# jammer.net
KiCad netlist of a schematic drawn in Altium Designer
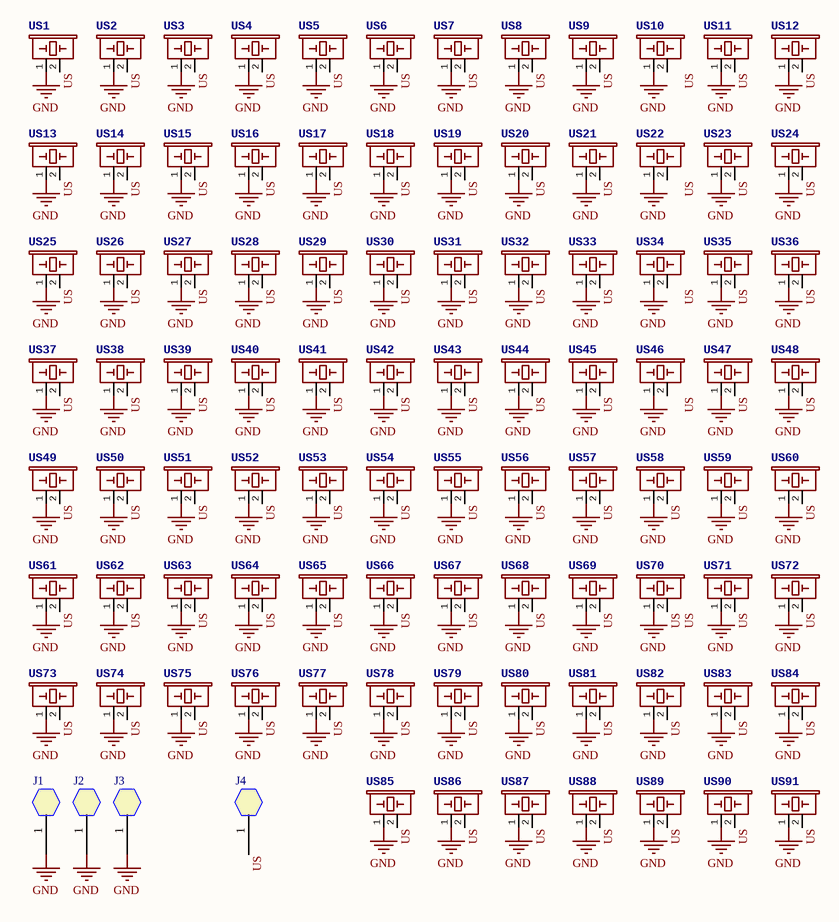
[diagram p0: jammer.SchDoc]

(export (version "E")
  (design (tool "Eeschema 10.0.6"))
  (components
    (comp (ref "J1")
      (value "NutSolder")
      (footprint "NutSolder")
      (libsource (lib "400PT160_2") (part "NutSolder"))
    )
    (comp (ref "J2")
      (value "NutSolder")
      (footprint "NutSolder")
      (libsource (lib "400PT160_2") (part "NutSolder"))
    )
    (comp (ref "J3")
      (value "NutSolder")
      (footprint "NutSolder")
      (libsource (lib "400PT160_2") (part "NutSolder"))
    )
    (comp (ref "J4")
      (value "NutSolder")
      (footprint "NutSolder")
      (libsource (lib "400PT160_2") (part "NutSolder"))
    )
    (comp (ref "US1")
      (value "Comment")
      (footprint "400PT1601")
      (fields (field (name "MP") "400PT160") (field (name "MF") "Prowave"))
      (libsource (lib "400PT160") (part "400PT160"))
    )
    (comp (ref "US2")
      (value "~")
      (footprint "400PT1601")
      (fields (field (name "MP") "400PT160") (field (name "MF") "Prowave"))
      (libsource (lib "400PT160") (part "400PT160"))
    )
    (comp (ref "US3")
      (value "Comment")
      (footprint "400PT1601")
      (fields (field (name "MP") "400PT160") (field (name "MF") "Prowave"))
      (libsource (lib "400PT160") (part "400PT160"))
    )
    (comp (ref "US4")
      (value "Comment")
      (footprint "400PT1601")
      (fields (field (name "MP") "400PT160") (field (name "MF") "Prowave"))
      (libsource (lib "400PT160") (part "400PT160"))
    )
    (comp (ref "US5")
      (value "Comment")
      (footprint "400PT1601")
      (fields (field (name "MP") "400PT160") (field (name "MF") "Prowave"))
      (libsource (lib "400PT160") (part "400PT160"))
    )
    (comp (ref "US6")
      (value "Comment")
      (footprint "400PT1601")
      (fields (field (name "MP") "400PT160") (field (name "MF") "Prowave"))
      (libsource (lib "400PT160") (part "400PT160"))
    )
    (comp (ref "US7")
      (value "Comment")
      (footprint "400PT1601")
      (fields (field (name "MP") "400PT160") (field (name "MF") "Prowave"))
      (libsource (lib "400PT160") (part "400PT160"))
    )
    (comp (ref "US8")
      (value "Comment")
      (footprint "400PT1601")
      (fields (field (name "MP") "400PT160") (field (name "MF") "Prowave"))
      (libsource (lib "400PT160") (part "400PT160"))
    )
    (comp (ref "US9")
      (value "Comment")
      (footprint "400PT1601")
      (fields (field (name "MP") "400PT160") (field (name "MF") "Prowave"))
      (libsource (lib "400PT160") (part "400PT160"))
    )
    (comp (ref "US10")
      (value "Comment")
      (footprint "400PT1601")
      (fields (field (name "MP") "400PT160") (field (name "MF") "Prowave"))
      (libsource (lib "400PT160") (part "400PT160"))
    )
    (comp (ref "US11")
      (value "Comment")
      (footprint "400PT1601")
      (fields (field (name "MP") "400PT160") (field (name "MF") "Prowave"))
      (libsource (lib "400PT160") (part "400PT160"))
    )
    (comp (ref "US12")
      (value "Comment")
      (footprint "400PT1601")
      (fields (field (name "MP") "400PT160") (field (name "MF") "Prowave"))
      (libsource (lib "400PT160") (part "400PT160"))
    )
    (comp (ref "US13")
      (value "Comment")
      (footprint "400PT1601")
      (fields (field (name "MP") "400PT160") (field (name "MF") "Prowave"))
      (libsource (lib "400PT160") (part "400PT160"))
    )
    (comp (ref "US14")
      (value "Comment")
      (footprint "400PT1601")
      (fields (field (name "MP") "400PT160") (field (name "MF") "Prowave"))
      (libsource (lib "400PT160") (part "400PT160"))
    )
    (comp (ref "US15")
      (value "Comment")
      (footprint "400PT1601")
      (fields (field (name "MP") "400PT160") (field (name "MF") "Prowave"))
      (libsource (lib "400PT160") (part "400PT160"))
    )
    (comp (ref "US16")
      (value "Comment")
      (footprint "400PT1601")
      (fields (field (name "MP") "400PT160") (field (name "MF") "Prowave"))
      (libsource (lib "400PT160") (part "400PT160"))
    )
    (comp (ref "US17")
      (value "Comment")
      (footprint "400PT1601")
      (fields (field (name "MP") "400PT160") (field (name "MF") "Prowave"))
      (libsource (lib "400PT160") (part "400PT160"))
    )
    (comp (ref "US18")
      (value "Comment")
      (footprint "400PT1601")
      (fields (field (name "MP") "400PT160") (field (name "MF") "Prowave"))
      (libsource (lib "400PT160") (part "400PT160"))
    )
    (comp (ref "US19")
      (value "Comment")
      (footprint "400PT1601")
      (fields (field (name "MP") "400PT160") (field (name "MF") "Prowave"))
      (libsource (lib "400PT160") (part "400PT160"))
    )
    (comp (ref "US20")
      (value "Comment")
      (footprint "400PT1601")
      (fields (field (name "MP") "400PT160") (field (name "MF") "Prowave"))
      (libsource (lib "400PT160") (part "400PT160"))
    )
    (comp (ref "US21")
      (value "Comment")
      (footprint "400PT1601")
      (fields (field (name "MP") "400PT160") (field (name "MF") "Prowave"))
      (libsource (lib "400PT160") (part "400PT160"))
    )
    (comp (ref "US22")
      (value "Comment")
      (footprint "400PT1601")
      (fields (field (name "MP") "400PT160") (field (name "MF") "Prowave"))
      (libsource (lib "400PT160") (part "400PT160"))
    )
    (comp (ref "US23")
      (value "Comment")
      (footprint "400PT1601")
      (fields (field (name "MP") "400PT160") (field (name "MF") "Prowave"))
      (libsource (lib "400PT160") (part "400PT160"))
    )
    (comp (ref "US24")
      (value "Comment")
      (footprint "400PT1601")
      (fields (field (name "MP") "400PT160") (field (name "MF") "Prowave"))
      (libsource (lib "400PT160") (part "400PT160"))
    )
    (comp (ref "US25")
      (value "Comment")
      (footprint "400PT1601")
      (fields (field (name "MP") "400PT160") (field (name "MF") "Prowave"))
      (libsource (lib "400PT160") (part "400PT160"))
    )
    (comp (ref "US26")
      (value "~")
      (footprint "400PT1601")
      (fields (field (name "MP") "400PT160") (field (name "MF") "Prowave"))
      (libsource (lib "400PT160") (part "400PT160"))
    )
    (comp (ref "US27")
      (value "Comment")
      (footprint "400PT1601")
      (fields (field (name "MP") "400PT160") (field (name "MF") "Prowave"))
      (libsource (lib "400PT160") (part "400PT160"))
    )
    (comp (ref "US28")
      (value "Comment")
      (footprint "400PT1601")
      (fields (field (name "MP") "400PT160") (field (name "MF") "Prowave"))
      (libsource (lib "400PT160") (part "400PT160"))
    )
    (comp (ref "US29")
      (value "Comment")
      (footprint "400PT1601")
      (fields (field (name "MP") "400PT160") (field (name "MF") "Prowave"))
      (libsource (lib "400PT160") (part "400PT160"))
    )
    (comp (ref "US30")
      (value "Comment")
      (footprint "400PT1601")
      (fields (field (name "MP") "400PT160") (field (name "MF") "Prowave"))
      (libsource (lib "400PT160") (part "400PT160"))
    )
    (comp (ref "US31")
      (value "Comment")
      (footprint "400PT1601")
      (fields (field (name "MP") "400PT160") (field (name "MF") "Prowave"))
      (libsource (lib "400PT160") (part "400PT160"))
    )
    (comp (ref "US32")
      (value "Comment")
      (footprint "400PT1601")
      (fields (field (name "MP") "400PT160") (field (name "MF") "Prowave"))
      (libsource (lib "400PT160") (part "400PT160"))
    )
    (comp (ref "US33")
      (value "Comment")
      (footprint "400PT1601")
      (fields (field (name "MP") "400PT160") (field (name "MF") "Prowave"))
      (libsource (lib "400PT160") (part "400PT160"))
    )
    (comp (ref "US34")
      (value "Comment")
      (footprint "400PT1601")
      (fields (field (name "MP") "400PT160") (field (name "MF") "Prowave"))
      (libsource (lib "400PT160") (part "400PT160"))
    )
    (comp (ref "US35")
      (value "Comment")
      (footprint "400PT1601")
      (fields (field (name "MP") "400PT160") (field (name "MF") "Prowave"))
      (libsource (lib "400PT160") (part "400PT160"))
    )
    (comp (ref "US36")
      (value "Comment")
      (footprint "400PT1601")
      (fields (field (name "MP") "400PT160") (field (name "MF") "Prowave"))
      (libsource (lib "400PT160") (part "400PT160"))
    )
    (comp (ref "US37")
      (value "Comment")
      (footprint "400PT1601")
      (fields (field (name "MP") "400PT160") (field (name "MF") "Prowave"))
      (libsource (lib "400PT160") (part "400PT160"))
    )
    (comp (ref "US38")
      (value "Comment")
      (footprint "400PT1601")
      (fields (field (name "MP") "400PT160") (field (name "MF") "Prowave"))
      (libsource (lib "400PT160") (part "400PT160"))
    )
    (comp (ref "US39")
      (value "Comment")
      (footprint "400PT1601")
      (fields (field (name "MP") "400PT160") (field (name "MF") "Prowave"))
      (libsource (lib "400PT160") (part "400PT160"))
    )
    (comp (ref "US40")
      (value "Comment")
      (footprint "400PT1601")
      (fields (field (name "MP") "400PT160") (field (name "MF") "Prowave"))
      (libsource (lib "400PT160") (part "400PT160"))
    )
    (comp (ref "US41")
      (value "Comment")
      (footprint "400PT1601")
      (fields (field (name "MP") "400PT160") (field (name "MF") "Prowave"))
      (libsource (lib "400PT160") (part "400PT160"))
    )
    (comp (ref "US42")
      (value "Comment")
      (footprint "400PT1601")
      (fields (field (name "MP") "400PT160") (field (name "MF") "Prowave"))
      (libsource (lib "400PT160") (part "400PT160"))
    )
    (comp (ref "US43")
      (value "Comment")
      (footprint "400PT1601")
      (fields (field (name "MP") "400PT160") (field (name "MF") "Prowave"))
      (libsource (lib "400PT160") (part "400PT160"))
    )
    (comp (ref "US44")
      (value "Comment")
      (footprint "400PT1601")
      (fields (field (name "MP") "400PT160") (field (name "MF") "Prowave"))
      (libsource (lib "400PT160") (part "400PT160"))
    )
    (comp (ref "US45")
      (value "Comment")
      (footprint "400PT1601")
      (fields (field (name "MP") "400PT160") (field (name "MF") "Prowave"))
      (libsource (lib "400PT160") (part "400PT160"))
    )
    (comp (ref "US46")
      (value "Comment")
      (footprint "400PT1601")
      (fields (field (name "MP") "400PT160") (field (name "MF") "Prowave"))
      (libsource (lib "400PT160") (part "400PT160"))
    )
    (comp (ref "US47")
      (value "Comment")
      (footprint "400PT1601")
      (fields (field (name "MP") "400PT160") (field (name "MF") "Prowave"))
      (libsource (lib "400PT160") (part "400PT160"))
    )
    (comp (ref "US48")
      (value "Comment")
      (footprint "400PT1601")
      (fields (field (name "MP") "400PT160") (field (name "MF") "Prowave"))
      (libsource (lib "400PT160") (part "400PT160"))
    )
    (comp (ref "US49")
      (value "Comment")
      (footprint "400PT1601")
      (fields (field (name "MP") "400PT160") (field (name "MF") "Prowave"))
      (libsource (lib "400PT160") (part "400PT160"))
    )
    (comp (ref "US50")
      (value "~")
      (footprint "400PT1601")
      (fields (field (name "MP") "400PT160") (field (name "MF") "Prowave"))
      (libsource (lib "400PT160") (part "400PT160"))
    )
    (comp (ref "US51")
      (value "Comment")
      (footprint "400PT1601")
      (fields (field (name "MP") "400PT160") (field (name "MF") "Prowave"))
      (libsource (lib "400PT160") (part "400PT160"))
    )
    (comp (ref "US52")
      (value "Comment")
      (footprint "400PT1601")
      (fields (field (name "MP") "400PT160") (field (name "MF") "Prowave"))
      (libsource (lib "400PT160") (part "400PT160"))
    )
    (comp (ref "US53")
      (value "Comment")
      (footprint "400PT1601")
      (fields (field (name "MP") "400PT160") (field (name "MF") "Prowave"))
      (libsource (lib "400PT160") (part "400PT160"))
    )
    (comp (ref "US54")
      (value "Comment")
      (footprint "400PT1601")
      (fields (field (name "MP") "400PT160") (field (name "MF") "Prowave"))
      (libsource (lib "400PT160") (part "400PT160"))
    )
    (comp (ref "US55")
      (value "Comment")
      (footprint "400PT1601")
      (fields (field (name "MP") "400PT160") (field (name "MF") "Prowave"))
      (libsource (lib "400PT160") (part "400PT160"))
    )
    (comp (ref "US56")
      (value "Comment")
      (footprint "400PT1601")
      (fields (field (name "MP") "400PT160") (field (name "MF") "Prowave"))
      (libsource (lib "400PT160") (part "400PT160"))
    )
    (comp (ref "US57")
      (value "Comment")
      (footprint "400PT1601")
      (fields (field (name "MP") "400PT160") (field (name "MF") "Prowave"))
      (libsource (lib "400PT160") (part "400PT160"))
    )
    (comp (ref "US58")
      (value "Comment")
      (footprint "400PT1601")
      (fields (field (name "MP") "400PT160") (field (name "MF") "Prowave"))
      (libsource (lib "400PT160") (part "400PT160"))
    )
    (comp (ref "US59")
      (value "Comment")
      (footprint "400PT1601")
      (fields (field (name "MP") "400PT160") (field (name "MF") "Prowave"))
      (libsource (lib "400PT160") (part "400PT160"))
    )
    (comp (ref "US60")
      (value "Comment")
      (footprint "400PT1601")
      (fields (field (name "MP") "400PT160") (field (name "MF") "Prowave"))
      (libsource (lib "400PT160") (part "400PT160"))
    )
    (comp (ref "US61")
      (value "Comment")
      (footprint "400PT1601")
      (fields (field (name "MP") "400PT160") (field (name "MF") "Prowave"))
      (libsource (lib "400PT160") (part "400PT160"))
    )
    (comp (ref "US62")
      (value "Comment")
      (footprint "400PT1601")
      (fields (field (name "MP") "400PT160") (field (name "MF") "Prowave"))
      (libsource (lib "400PT160") (part "400PT160"))
    )
    (comp (ref "US63")
      (value "Comment")
      (footprint "400PT1601")
      (fields (field (name "MP") "400PT160") (field (name "MF") "Prowave"))
      (libsource (lib "400PT160") (part "400PT160"))
    )
    (comp (ref "US64")
      (value "~")
      (footprint "400PT1601")
      (fields (field (name "MP") "400PT160") (field (name "MF") "Prowave"))
      (libsource (lib "400PT160") (part "400PT160"))
    )
    (comp (ref "US65")
      (value "~")
      (footprint "400PT1601")
      (fields (field (name "MP") "400PT160") (field (name "MF") "Prowave"))
      (libsource (lib "400PT160") (part "400PT160"))
    )
    (comp (ref "US66")
      (value "~")
      (footprint "400PT1601")
      (fields (field (name "MP") "400PT160") (field (name "MF") "Prowave"))
      (libsource (lib "400PT160") (part "400PT160"))
    )
    (comp (ref "US67")
      (value "~")
      (footprint "400PT1601")
      (fields (field (name "MP") "400PT160") (field (name "MF") "Prowave"))
      (libsource (lib "400PT160") (part "400PT160"))
    )
    (comp (ref "US68")
      (value "Comment")
      (footprint "400PT1601")
      (fields (field (name "MP") "400PT160") (field (name "MF") "Prowave"))
      (libsource (lib "400PT160") (part "400PT160"))
    )
    (comp (ref "US69")
      (value "Comment")
      (footprint "400PT1601")
      (fields (field (name "MP") "400PT160") (field (name "MF") "Prowave"))
      (libsource (lib "400PT160") (part "400PT160"))
    )
    (comp (ref "US70")
      (value "Comment")
      (footprint "400PT1601")
      (fields (field (name "MP") "400PT160") (field (name "MF") "Prowave"))
      (libsource (lib "400PT160") (part "400PT160"))
    )
    (comp (ref "US71")
      (value "Comment")
      (footprint "400PT1601")
      (fields (field (name "MP") "400PT160") (field (name "MF") "Prowave"))
      (libsource (lib "400PT160") (part "400PT160"))
    )
    (comp (ref "US72")
      (value "Comment")
      (footprint "400PT1601")
      (fields (field (name "MP") "400PT160") (field (name "MF") "Prowave"))
      (libsource (lib "400PT160") (part "400PT160"))
    )
    (comp (ref "US73")
      (value "Comment")
      (footprint "400PT1601")
      (fields (field (name "MP") "400PT160") (field (name "MF") "Prowave"))
      (libsource (lib "400PT160") (part "400PT160"))
    )
    (comp (ref "US74")
      (value "Comment")
      (footprint "400PT1601")
      (fields (field (name "MP") "400PT160") (field (name "MF") "Prowave"))
      (libsource (lib "400PT160") (part "400PT160"))
    )
    (comp (ref "US75")
      (value "Comment")
      (footprint "400PT1601")
      (fields (field (name "MP") "400PT160") (field (name "MF") "Prowave"))
      (libsource (lib "400PT160") (part "400PT160"))
    )
    (comp (ref "US76")
      (value "Comment")
      (footprint "400PT1601")
      (fields (field (name "MP") "400PT160") (field (name "MF") "Prowave"))
      (libsource (lib "400PT160") (part "400PT160"))
    )
    (comp (ref "US77")
      (value "Comment")
      (footprint "400PT1601")
      (fields (field (name "MP") "400PT160") (field (name "MF") "Prowave"))
      (libsource (lib "400PT160") (part "400PT160"))
    )
    (comp (ref "US78")
      (value "Comment")
      (footprint "400PT1601")
      (fields (field (name "MP") "400PT160") (field (name "MF") "Prowave"))
      (libsource (lib "400PT160") (part "400PT160"))
    )
    (comp (ref "US79")
      (value "Comment")
      (footprint "400PT1601")
      (fields (field (name "MP") "400PT160") (field (name "MF") "Prowave"))
      (libsource (lib "400PT160") (part "400PT160"))
    )
    (comp (ref "US80")
      (value "Comment")
      (footprint "400PT1601")
      (fields (field (name "MP") "400PT160") (field (name "MF") "Prowave"))
      (libsource (lib "400PT160") (part "400PT160"))
    )
    (comp (ref "US81")
      (value "Comment")
      (footprint "400PT1601")
      (fields (field (name "MP") "400PT160") (field (name "MF") "Prowave"))
      (libsource (lib "400PT160") (part "400PT160"))
    )
    (comp (ref "US82")
      (value "Comment")
      (footprint "400PT1601")
      (fields (field (name "MP") "400PT160") (field (name "MF") "Prowave"))
      (libsource (lib "400PT160") (part "400PT160"))
    )
    (comp (ref "US83")
      (value "Comment")
      (footprint "400PT1601")
      (fields (field (name "MP") "400PT160") (field (name "MF") "Prowave"))
      (libsource (lib "400PT160") (part "400PT160"))
    )
    (comp (ref "US84")
      (value "Comment")
      (footprint "400PT1601")
      (fields (field (name "MP") "400PT160") (field (name "MF") "Prowave"))
      (libsource (lib "400PT160") (part "400PT160"))
    )
    (comp (ref "US85")
      (value "Comment")
      (footprint "400PT1601")
      (fields (field (name "MP") "400PT160") (field (name "MF") "Prowave"))
      (libsource (lib "400PT160") (part "400PT160"))
    )
    (comp (ref "US86")
      (value "Comment")
      (footprint "400PT1601")
      (fields (field (name "MP") "400PT160") (field (name "MF") "Prowave"))
      (libsource (lib "400PT160") (part "400PT160"))
    )
    (comp (ref "US87")
      (value "Comment")
      (footprint "400PT1601")
      (fields (field (name "MP") "400PT160") (field (name "MF") "Prowave"))
      (libsource (lib "400PT160") (part "400PT160"))
    )
    (comp (ref "US88")
      (value "Comment")
      (footprint "400PT1601")
      (fields (field (name "MP") "400PT160") (field (name "MF") "Prowave"))
      (libsource (lib "400PT160") (part "400PT160"))
    )
    (comp (ref "US89")
      (value "Comment")
      (footprint "400PT1601")
      (fields (field (name "MP") "400PT160") (field (name "MF") "Prowave"))
      (libsource (lib "400PT160") (part "400PT160"))
    )
    (comp (ref "US90")
      (value "Comment")
      (footprint "400PT1601")
      (fields (field (name "MP") "400PT160") (field (name "MF") "Prowave"))
      (libsource (lib "400PT160") (part "400PT160"))
    )
    (comp (ref "US91")
      (value "Comment")
      (footprint "400PT1601")
      (fields (field (name "MP") "400PT160") (field (name "MF") "Prowave"))
      (libsource (lib "400PT160") (part "400PT160"))
    )
  )
  (nets
    (net (code "1") (name "/US") (class "Default")
      (node (ref "J4") (pin "1") (pinfunction "1_1") (pintype "passive"))
      (node (ref "US1") (pin "2") (pinfunction "2_2") (pintype "passive"))
      (node (ref "US11") (pin "2") (pinfunction "2_2") (pintype "passive"))
      (node (ref "US12") (pin "2") (pinfunction "2_2") (pintype "passive"))
      (node (ref "US13") (pin "2") (pinfunction "2_2") (pintype "passive"))
      (node (ref "US14") (pin "2") (pinfunction "2_2") (pintype "passive"))
      (node (ref "US15") (pin "2") (pinfunction "2_2") (pintype "passive"))
      (node (ref "US16") (pin "2") (pinfunction "2_2") (pintype "passive"))
      (node (ref "US17") (pin "2") (pinfunction "2_2") (pintype "passive"))
      (node (ref "US18") (pin "2") (pinfunction "2_2") (pintype "passive"))
      (node (ref "US19") (pin "2") (pinfunction "2_2") (pintype "passive"))
      (node (ref "US2") (pin "2") (pinfunction "2_2") (pintype "passive"))
      (node (ref "US20") (pin "2") (pinfunction "2_2") (pintype "passive"))
      (node (ref "US21") (pin "2") (pinfunction "2_2") (pintype "passive"))
      (node (ref "US23") (pin "2") (pinfunction "2_2") (pintype "passive"))
      (node (ref "US24") (pin "2") (pinfunction "2_2") (pintype "passive"))
      (node (ref "US25") (pin "2") (pinfunction "2_2") (pintype "passive"))
      (node (ref "US26") (pin "2") (pinfunction "2_2") (pintype "passive"))
      (node (ref "US27") (pin "2") (pinfunction "2_2") (pintype "passive"))
      (node (ref "US28") (pin "2") (pinfunction "2_2") (pintype "passive"))
      (node (ref "US29") (pin "2") (pinfunction "2_2") (pintype "passive"))
      (node (ref "US3") (pin "2") (pinfunction "2_2") (pintype "passive"))
      (node (ref "US30") (pin "2") (pinfunction "2_2") (pintype "passive"))
      (node (ref "US31") (pin "2") (pinfunction "2_2") (pintype "passive"))
      (node (ref "US32") (pin "2") (pinfunction "2_2") (pintype "passive"))
      (node (ref "US33") (pin "2") (pinfunction "2_2") (pintype "passive"))
      (node (ref "US35") (pin "2") (pinfunction "2_2") (pintype "passive"))
      (node (ref "US36") (pin "2") (pinfunction "2_2") (pintype "passive"))
      (node (ref "US37") (pin "2") (pinfunction "2_2") (pintype "passive"))
      (node (ref "US38") (pin "2") (pinfunction "2_2") (pintype "passive"))
      (node (ref "US39") (pin "2") (pinfunction "2_2") (pintype "passive"))
      (node (ref "US4") (pin "2") (pinfunction "2_2") (pintype "passive"))
      (node (ref "US40") (pin "2") (pinfunction "2_2") (pintype "passive"))
      (node (ref "US41") (pin "2") (pinfunction "2_2") (pintype "passive"))
      (node (ref "US42") (pin "2") (pinfunction "2_2") (pintype "passive"))
      (node (ref "US43") (pin "2") (pinfunction "2_2") (pintype "passive"))
      (node (ref "US44") (pin "2") (pinfunction "2_2") (pintype "passive"))
      (node (ref "US45") (pin "2") (pinfunction "2_2") (pintype "passive"))
      (node (ref "US47") (pin "2") (pinfunction "2_2") (pintype "passive"))
      (node (ref "US48") (pin "2") (pinfunction "2_2") (pintype "passive"))
      (node (ref "US49") (pin "2") (pinfunction "2_2") (pintype "passive"))
      (node (ref "US5") (pin "2") (pinfunction "2_2") (pintype "passive"))
      (node (ref "US50") (pin "2") (pinfunction "2_2") (pintype "passive"))
      (node (ref "US51") (pin "2") (pinfunction "2_2") (pintype "passive"))
      (node (ref "US52") (pin "2") (pinfunction "2_2") (pintype "passive"))
      (node (ref "US53") (pin "2") (pinfunction "2_2") (pintype "passive"))
      (node (ref "US54") (pin "2") (pinfunction "2_2") (pintype "passive"))
      (node (ref "US55") (pin "2") (pinfunction "2_2") (pintype "passive"))
      (node (ref "US56") (pin "2") (pinfunction "2_2") (pintype "passive"))
      (node (ref "US57") (pin "2") (pinfunction "2_2") (pintype "passive"))
      (node (ref "US58") (pin "2") (pinfunction "2_2") (pintype "passive"))
      (node (ref "US59") (pin "2") (pinfunction "2_2") (pintype "passive"))
      (node (ref "US6") (pin "2") (pinfunction "2_2") (pintype "passive"))
      (node (ref "US60") (pin "2") (pinfunction "2_2") (pintype "passive"))
      (node (ref "US61") (pin "2") (pinfunction "2_2") (pintype "passive"))
      (node (ref "US62") (pin "2") (pinfunction "2_2") (pintype "passive"))
      (node (ref "US63") (pin "2") (pinfunction "2_2") (pintype "passive"))
      (node (ref "US64") (pin "2") (pinfunction "2_2") (pintype "passive"))
      (node (ref "US65") (pin "2") (pinfunction "2_2") (pintype "passive"))
      (node (ref "US66") (pin "2") (pinfunction "2_2") (pintype "passive"))
      (node (ref "US67") (pin "2") (pinfunction "2_2") (pintype "passive"))
      (node (ref "US68") (pin "2") (pinfunction "2_2") (pintype "passive"))
      (node (ref "US69") (pin "2") (pinfunction "2_2") (pintype "passive"))
      (node (ref "US7") (pin "2") (pinfunction "2_2") (pintype "passive"))
      (node (ref "US70") (pin "2") (pinfunction "2_2") (pintype "passive"))
      (node (ref "US71") (pin "2") (pinfunction "2_2") (pintype "passive"))
      (node (ref "US72") (pin "2") (pinfunction "2_2") (pintype "passive"))
      (node (ref "US73") (pin "2") (pinfunction "2_2") (pintype "passive"))
      (node (ref "US74") (pin "2") (pinfunction "2_2") (pintype "passive"))
      (node (ref "US75") (pin "2") (pinfunction "2_2") (pintype "passive"))
      (node (ref "US76") (pin "2") (pinfunction "2_2") (pintype "passive"))
      (node (ref "US77") (pin "2") (pinfunction "2_2") (pintype "passive"))
      (node (ref "US78") (pin "2") (pinfunction "2_2") (pintype "passive"))
      (node (ref "US79") (pin "2") (pinfunction "2_2") (pintype "passive"))
      (node (ref "US8") (pin "2") (pinfunction "2_2") (pintype "passive"))
      (node (ref "US80") (pin "2") (pinfunction "2_2") (pintype "passive"))
      (node (ref "US81") (pin "2") (pinfunction "2_2") (pintype "passive"))
      (node (ref "US82") (pin "2") (pinfunction "2_2") (pintype "passive"))
      (node (ref "US83") (pin "2") (pinfunction "2_2") (pintype "passive"))
      (node (ref "US84") (pin "2") (pinfunction "2_2") (pintype "passive"))
      (node (ref "US85") (pin "2") (pinfunction "2_2") (pintype "passive"))
      (node (ref "US86") (pin "2") (pinfunction "2_2") (pintype "passive"))
      (node (ref "US87") (pin "2") (pinfunction "2_2") (pintype "passive"))
      (node (ref "US88") (pin "2") (pinfunction "2_2") (pintype "passive"))
      (node (ref "US89") (pin "2") (pinfunction "2_2") (pintype "passive"))
      (node (ref "US9") (pin "2") (pinfunction "2_2") (pintype "passive"))
      (node (ref "US90") (pin "2") (pinfunction "2_2") (pintype "passive"))
      (node (ref "US91") (pin "2") (pinfunction "2_2") (pintype "passive"))
    )
    (net (code "2") (name "GND") (class "Default")
      (node (ref "J1") (pin "1") (pinfunction "1_1") (pintype "passive"))
      (node (ref "J2") (pin "1") (pinfunction "1_1") (pintype "passive"))
      (node (ref "J3") (pin "1") (pinfunction "1_1") (pintype "passive"))
      (node (ref "US1") (pin "1") (pinfunction "1_1") (pintype "passive"))
      (node (ref "US10") (pin "1") (pinfunction "1_1") (pintype "passive"))
      (node (ref "US11") (pin "1") (pinfunction "1_1") (pintype "passive"))
      (node (ref "US12") (pin "1") (pinfunction "1_1") (pintype "passive"))
      (node (ref "US13") (pin "1") (pinfunction "1_1") (pintype "passive"))
      (node (ref "US14") (pin "1") (pinfunction "1_1") (pintype "passive"))
      (node (ref "US15") (pin "1") (pinfunction "1_1") (pintype "passive"))
      (node (ref "US16") (pin "1") (pinfunction "1_1") (pintype "passive"))
      (node (ref "US17") (pin "1") (pinfunction "1_1") (pintype "passive"))
      (node (ref "US18") (pin "1") (pinfunction "1_1") (pintype "passive"))
      (node (ref "US19") (pin "1") (pinfunction "1_1") (pintype "passive"))
      (node (ref "US2") (pin "1") (pinfunction "1_1") (pintype "passive"))
      (node (ref "US20") (pin "1") (pinfunction "1_1") (pintype "passive"))
      (node (ref "US21") (pin "1") (pinfunction "1_1") (pintype "passive"))
      (node (ref "US22") (pin "1") (pinfunction "1_1") (pintype "passive"))
      (node (ref "US23") (pin "1") (pinfunction "1_1") (pintype "passive"))
      (node (ref "US24") (pin "1") (pinfunction "1_1") (pintype "passive"))
      (node (ref "US25") (pin "1") (pinfunction "1_1") (pintype "passive"))
      (node (ref "US26") (pin "1") (pinfunction "1_1") (pintype "passive"))
      (node (ref "US27") (pin "1") (pinfunction "1_1") (pintype "passive"))
      (node (ref "US28") (pin "1") (pinfunction "1_1") (pintype "passive"))
      (node (ref "US29") (pin "1") (pinfunction "1_1") (pintype "passive"))
      (node (ref "US3") (pin "1") (pinfunction "1_1") (pintype "passive"))
      (node (ref "US30") (pin "1") (pinfunction "1_1") (pintype "passive"))
      (node (ref "US31") (pin "1") (pinfunction "1_1") (pintype "passive"))
      (node (ref "US32") (pin "1") (pinfunction "1_1") (pintype "passive"))
      (node (ref "US33") (pin "1") (pinfunction "1_1") (pintype "passive"))
      (node (ref "US34") (pin "1") (pinfunction "1_1") (pintype "passive"))
      (node (ref "US35") (pin "1") (pinfunction "1_1") (pintype "passive"))
      (node (ref "US36") (pin "1") (pinfunction "1_1") (pintype "passive"))
      (node (ref "US37") (pin "1") (pinfunction "1_1") (pintype "passive"))
      (node (ref "US38") (pin "1") (pinfunction "1_1") (pintype "passive"))
      (node (ref "US39") (pin "1") (pinfunction "1_1") (pintype "passive"))
      (node (ref "US4") (pin "1") (pinfunction "1_1") (pintype "passive"))
      (node (ref "US40") (pin "1") (pinfunction "1_1") (pintype "passive"))
      (node (ref "US41") (pin "1") (pinfunction "1_1") (pintype "passive"))
      (node (ref "US42") (pin "1") (pinfunction "1_1") (pintype "passive"))
      (node (ref "US43") (pin "1") (pinfunction "1_1") (pintype "passive"))
      (node (ref "US44") (pin "1") (pinfunction "1_1") (pintype "passive"))
      (node (ref "US45") (pin "1") (pinfunction "1_1") (pintype "passive"))
      (node (ref "US46") (pin "1") (pinfunction "1_1") (pintype "passive"))
      (node (ref "US47") (pin "1") (pinfunction "1_1") (pintype "passive"))
      (node (ref "US48") (pin "1") (pinfunction "1_1") (pintype "passive"))
      (node (ref "US49") (pin "1") (pinfunction "1_1") (pintype "passive"))
      (node (ref "US5") (pin "1") (pinfunction "1_1") (pintype "passive"))
      (node (ref "US50") (pin "1") (pinfunction "1_1") (pintype "passive"))
      (node (ref "US51") (pin "1") (pinfunction "1_1") (pintype "passive"))
      (node (ref "US52") (pin "1") (pinfunction "1_1") (pintype "passive"))
      (node (ref "US53") (pin "1") (pinfunction "1_1") (pintype "passive"))
      (node (ref "US54") (pin "1") (pinfunction "1_1") (pintype "passive"))
      (node (ref "US55") (pin "1") (pinfunction "1_1") (pintype "passive"))
      (node (ref "US56") (pin "1") (pinfunction "1_1") (pintype "passive"))
      (node (ref "US57") (pin "1") (pinfunction "1_1") (pintype "passive"))
      (node (ref "US58") (pin "1") (pinfunction "1_1") (pintype "passive"))
      (node (ref "US59") (pin "1") (pinfunction "1_1") (pintype "passive"))
      (node (ref "US6") (pin "1") (pinfunction "1_1") (pintype "passive"))
      (node (ref "US60") (pin "1") (pinfunction "1_1") (pintype "passive"))
      (node (ref "US61") (pin "1") (pinfunction "1_1") (pintype "passive"))
      (node (ref "US62") (pin "1") (pinfunction "1_1") (pintype "passive"))
      (node (ref "US63") (pin "1") (pinfunction "1_1") (pintype "passive"))
      (node (ref "US64") (pin "1") (pinfunction "1_1") (pintype "passive"))
      (node (ref "US65") (pin "1") (pinfunction "1_1") (pintype "passive"))
      (node (ref "US66") (pin "1") (pinfunction "1_1") (pintype "passive"))
      (node (ref "US67") (pin "1") (pinfunction "1_1") (pintype "passive"))
      (node (ref "US68") (pin "1") (pinfunction "1_1") (pintype "passive"))
      (node (ref "US69") (pin "1") (pinfunction "1_1") (pintype "passive"))
      (node (ref "US7") (pin "1") (pinfunction "1_1") (pintype "passive"))
      (node (ref "US70") (pin "1") (pinfunction "1_1") (pintype "passive"))
      (node (ref "US71") (pin "1") (pinfunction "1_1") (pintype "passive"))
      (node (ref "US72") (pin "1") (pinfunction "1_1") (pintype "passive"))
      (node (ref "US73") (pin "1") (pinfunction "1_1") (pintype "passive"))
      (node (ref "US74") (pin "1") (pinfunction "1_1") (pintype "passive"))
      (node (ref "US75") (pin "1") (pinfunction "1_1") (pintype "passive"))
      (node (ref "US76") (pin "1") (pinfunction "1_1") (pintype "passive"))
      (node (ref "US77") (pin "1") (pinfunction "1_1") (pintype "passive"))
      (node (ref "US78") (pin "1") (pinfunction "1_1") (pintype "passive"))
      (node (ref "US79") (pin "1") (pinfunction "1_1") (pintype "passive"))
      (node (ref "US8") (pin "1") (pinfunction "1_1") (pintype "passive"))
      (node (ref "US80") (pin "1") (pinfunction "1_1") (pintype "passive"))
      (node (ref "US81") (pin "1") (pinfunction "1_1") (pintype "passive"))
      (node (ref "US82") (pin "1") (pinfunction "1_1") (pintype "passive"))
      (node (ref "US83") (pin "1") (pinfunction "1_1") (pintype "passive"))
      (node (ref "US84") (pin "1") (pinfunction "1_1") (pintype "passive"))
      (node (ref "US85") (pin "1") (pinfunction "1_1") (pintype "passive"))
      (node (ref "US86") (pin "1") (pinfunction "1_1") (pintype "passive"))
      (node (ref "US87") (pin "1") (pinfunction "1_1") (pintype "passive"))
      (node (ref "US88") (pin "1") (pinfunction "1_1") (pintype "passive"))
      (node (ref "US89") (pin "1") (pinfunction "1_1") (pintype "passive"))
      (node (ref "US9") (pin "1") (pinfunction "1_1") (pintype "passive"))
      (node (ref "US90") (pin "1") (pinfunction "1_1") (pintype "passive"))
      (node (ref "US91") (pin "1") (pinfunction "1_1") (pintype "passive"))
    )
    (net (code "3") (name "unconnected-(US10-Pad2)") (class "Default")
      (node (ref "US10") (pin "2") (pinfunction "2_2") (pintype "passive"))
    )
    (net (code "4") (name "unconnected-(US22-Pad2)") (class "Default")
      (node (ref "US22") (pin "2") (pinfunction "2_2") (pintype "passive"))
    )
    (net (code "5") (name "unconnected-(US34-Pad2)") (class "Default")
      (node (ref "US34") (pin "2") (pinfunction "2_2") (pintype "passive"))
    )
    (net (code "6") (name "unconnected-(US46-Pad2)") (class "Default")
      (node (ref "US46") (pin "2") (pinfunction "2_2") (pintype "passive"))
    )
  )
)
